# rgb_corin.net
KiCad netlist of a schematic drawn in Altium Designer
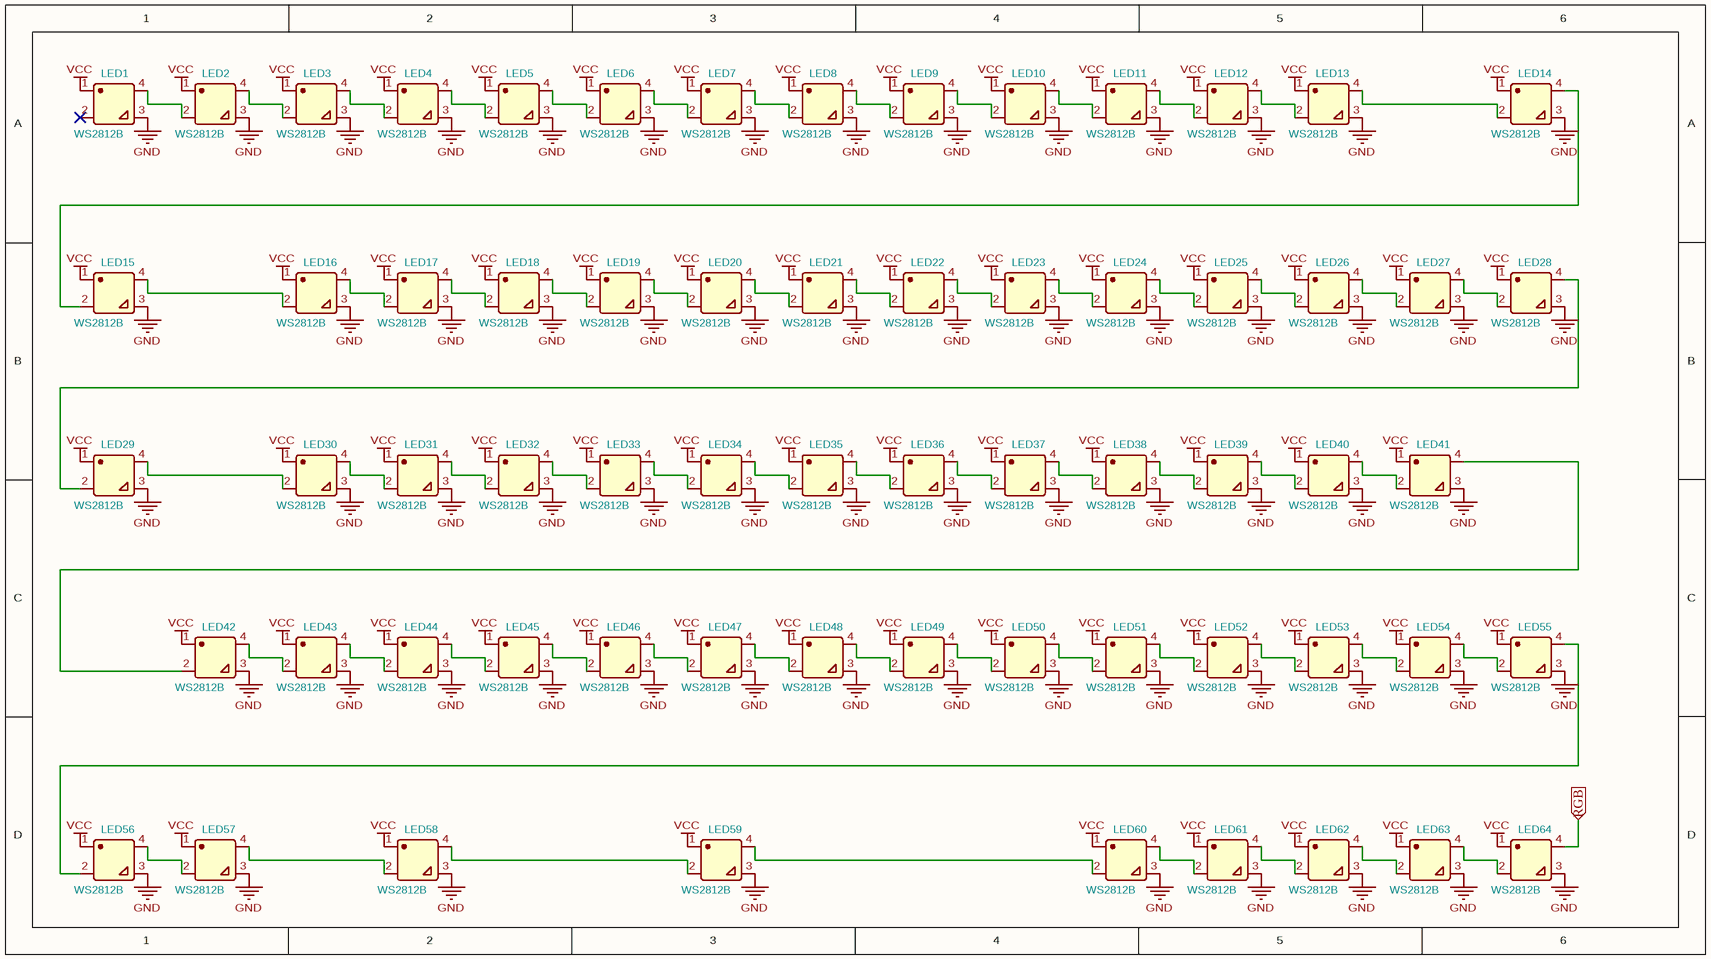
[diagram p0: rgb_corin.schdoc]

(export (version "E")
  (design (tool "Eeschema 10.0.6"))
  (components
    (comp (ref "LED1")
      (value "WS2812B")
      (fields (field (name "CONTRIBUTOR") "Longnald"))
      (libsource (lib "altium-import") (part "root_0_WS2812B_"))
    )
    (comp (ref "LED2")
      (value "WS2812B")
      (fields (field (name "CONTRIBUTOR") "Longnald"))
      (libsource (lib "altium-import") (part "root_0_WS2812B_"))
    )
    (comp (ref "LED3")
      (value "WS2812B")
      (fields (field (name "CONTRIBUTOR") "Longnald"))
      (libsource (lib "altium-import") (part "root_0_WS2812B_"))
    )
    (comp (ref "LED4")
      (value "WS2812B")
      (fields (field (name "CONTRIBUTOR") "Longnald"))
      (libsource (lib "altium-import") (part "root_0_WS2812B_"))
    )
    (comp (ref "LED5")
      (value "WS2812B")
      (fields (field (name "CONTRIBUTOR") "Longnald"))
      (libsource (lib "altium-import") (part "root_0_WS2812B_"))
    )
    (comp (ref "LED6")
      (value "WS2812B")
      (fields (field (name "CONTRIBUTOR") "Longnald"))
      (libsource (lib "altium-import") (part "root_0_WS2812B_"))
    )
    (comp (ref "LED7")
      (value "WS2812B")
      (fields (field (name "CONTRIBUTOR") "Longnald"))
      (libsource (lib "altium-import") (part "root_0_WS2812B_"))
    )
    (comp (ref "LED8")
      (value "WS2812B")
      (fields (field (name "CONTRIBUTOR") "Longnald"))
      (libsource (lib "altium-import") (part "root_0_WS2812B_"))
    )
    (comp (ref "LED9")
      (value "WS2812B")
      (fields (field (name "CONTRIBUTOR") "Longnald"))
      (libsource (lib "altium-import") (part "root_0_WS2812B_"))
    )
    (comp (ref "LED10")
      (value "WS2812B")
      (fields (field (name "CONTRIBUTOR") "Longnald"))
      (libsource (lib "altium-import") (part "root_0_WS2812B_"))
    )
    (comp (ref "LED11")
      (value "WS2812B")
      (fields (field (name "CONTRIBUTOR") "Longnald"))
      (libsource (lib "altium-import") (part "root_0_WS2812B_"))
    )
    (comp (ref "LED12")
      (value "WS2812B")
      (fields (field (name "CONTRIBUTOR") "Longnald"))
      (libsource (lib "altium-import") (part "root_0_WS2812B_"))
    )
    (comp (ref "LED13")
      (value "WS2812B")
      (fields (field (name "CONTRIBUTOR") "Longnald"))
      (libsource (lib "altium-import") (part "root_0_WS2812B_"))
    )
    (comp (ref "LED14")
      (value "WS2812B")
      (fields (field (name "CONTRIBUTOR") "Longnald"))
      (libsource (lib "altium-import") (part "root_0_WS2812B_"))
    )
    (comp (ref "LED15")
      (value "WS2812B")
      (fields (field (name "CONTRIBUTOR") "Longnald"))
      (libsource (lib "altium-import") (part "root_0_WS2812B_"))
    )
    (comp (ref "LED16")
      (value "WS2812B")
      (fields (field (name "CONTRIBUTOR") "Longnald"))
      (libsource (lib "altium-import") (part "root_0_WS2812B_"))
    )
    (comp (ref "LED17")
      (value "WS2812B")
      (fields (field (name "CONTRIBUTOR") "Longnald"))
      (libsource (lib "altium-import") (part "root_0_WS2812B_"))
    )
    (comp (ref "LED18")
      (value "WS2812B")
      (fields (field (name "CONTRIBUTOR") "Longnald"))
      (libsource (lib "altium-import") (part "root_0_WS2812B_"))
    )
    (comp (ref "LED19")
      (value "WS2812B")
      (fields (field (name "CONTRIBUTOR") "Longnald"))
      (libsource (lib "altium-import") (part "root_0_WS2812B_"))
    )
    (comp (ref "LED20")
      (value "WS2812B")
      (fields (field (name "CONTRIBUTOR") "Longnald"))
      (libsource (lib "altium-import") (part "root_0_WS2812B_"))
    )
    (comp (ref "LED21")
      (value "WS2812B")
      (fields (field (name "CONTRIBUTOR") "Longnald"))
      (libsource (lib "altium-import") (part "root_0_WS2812B_"))
    )
    (comp (ref "LED22")
      (value "WS2812B")
      (fields (field (name "CONTRIBUTOR") "Longnald"))
      (libsource (lib "altium-import") (part "root_0_WS2812B_"))
    )
    (comp (ref "LED23")
      (value "WS2812B")
      (fields (field (name "CONTRIBUTOR") "Longnald"))
      (libsource (lib "altium-import") (part "root_0_WS2812B_"))
    )
    (comp (ref "LED24")
      (value "WS2812B")
      (fields (field (name "CONTRIBUTOR") "Longnald"))
      (libsource (lib "altium-import") (part "root_0_WS2812B_"))
    )
    (comp (ref "LED25")
      (value "WS2812B")
      (fields (field (name "CONTRIBUTOR") "Longnald"))
      (libsource (lib "altium-import") (part "root_0_WS2812B_"))
    )
    (comp (ref "LED26")
      (value "WS2812B")
      (fields (field (name "CONTRIBUTOR") "Longnald"))
      (libsource (lib "altium-import") (part "root_0_WS2812B_"))
    )
    (comp (ref "LED27")
      (value "WS2812B")
      (fields (field (name "CONTRIBUTOR") "Longnald"))
      (libsource (lib "altium-import") (part "root_0_WS2812B_"))
    )
    (comp (ref "LED28")
      (value "WS2812B")
      (fields (field (name "CONTRIBUTOR") "Longnald"))
      (libsource (lib "altium-import") (part "root_0_WS2812B_"))
    )
    (comp (ref "LED29")
      (value "WS2812B")
      (fields (field (name "CONTRIBUTOR") "Longnald"))
      (libsource (lib "altium-import") (part "root_0_WS2812B_"))
    )
    (comp (ref "LED30")
      (value "WS2812B")
      (fields (field (name "CONTRIBUTOR") "Longnald"))
      (libsource (lib "altium-import") (part "root_0_WS2812B_"))
    )
    (comp (ref "LED31")
      (value "WS2812B")
      (fields (field (name "CONTRIBUTOR") "Longnald"))
      (libsource (lib "altium-import") (part "root_0_WS2812B_"))
    )
    (comp (ref "LED32")
      (value "WS2812B")
      (fields (field (name "CONTRIBUTOR") "Longnald"))
      (libsource (lib "altium-import") (part "root_0_WS2812B_"))
    )
    (comp (ref "LED33")
      (value "WS2812B")
      (fields (field (name "CONTRIBUTOR") "Longnald"))
      (libsource (lib "altium-import") (part "root_0_WS2812B_"))
    )
    (comp (ref "LED34")
      (value "WS2812B")
      (fields (field (name "CONTRIBUTOR") "Longnald"))
      (libsource (lib "altium-import") (part "root_0_WS2812B_"))
    )
    (comp (ref "LED35")
      (value "WS2812B")
      (fields (field (name "CONTRIBUTOR") "Longnald"))
      (libsource (lib "altium-import") (part "root_0_WS2812B_"))
    )
    (comp (ref "LED36")
      (value "WS2812B")
      (fields (field (name "CONTRIBUTOR") "Longnald"))
      (libsource (lib "altium-import") (part "root_0_WS2812B_"))
    )
    (comp (ref "LED37")
      (value "WS2812B")
      (fields (field (name "CONTRIBUTOR") "Longnald"))
      (libsource (lib "altium-import") (part "root_0_WS2812B_"))
    )
    (comp (ref "LED38")
      (value "WS2812B")
      (fields (field (name "CONTRIBUTOR") "Longnald"))
      (libsource (lib "altium-import") (part "root_0_WS2812B_"))
    )
    (comp (ref "LED39")
      (value "WS2812B")
      (fields (field (name "CONTRIBUTOR") "Longnald"))
      (libsource (lib "altium-import") (part "root_0_WS2812B_"))
    )
    (comp (ref "LED40")
      (value "WS2812B")
      (fields (field (name "CONTRIBUTOR") "Longnald"))
      (libsource (lib "altium-import") (part "root_0_WS2812B_"))
    )
    (comp (ref "LED41")
      (value "WS2812B")
      (fields (field (name "CONTRIBUTOR") "Longnald"))
      (libsource (lib "altium-import") (part "root_0_WS2812B_"))
    )
    (comp (ref "LED42")
      (value "WS2812B")
      (fields (field (name "CONTRIBUTOR") "Longnald"))
      (libsource (lib "altium-import") (part "root_0_WS2812B_"))
    )
    (comp (ref "LED43")
      (value "WS2812B")
      (fields (field (name "CONTRIBUTOR") "Longnald"))
      (libsource (lib "altium-import") (part "root_0_WS2812B_"))
    )
    (comp (ref "LED44")
      (value "WS2812B")
      (fields (field (name "CONTRIBUTOR") "Longnald"))
      (libsource (lib "altium-import") (part "root_0_WS2812B_"))
    )
    (comp (ref "LED45")
      (value "WS2812B")
      (fields (field (name "CONTRIBUTOR") "Longnald"))
      (libsource (lib "altium-import") (part "root_0_WS2812B_"))
    )
    (comp (ref "LED46")
      (value "WS2812B")
      (fields (field (name "CONTRIBUTOR") "Longnald"))
      (libsource (lib "altium-import") (part "root_0_WS2812B_"))
    )
    (comp (ref "LED47")
      (value "WS2812B")
      (fields (field (name "CONTRIBUTOR") "Longnald"))
      (libsource (lib "altium-import") (part "root_0_WS2812B_"))
    )
    (comp (ref "LED48")
      (value "WS2812B")
      (fields (field (name "CONTRIBUTOR") "Longnald"))
      (libsource (lib "altium-import") (part "root_0_WS2812B_"))
    )
    (comp (ref "LED49")
      (value "WS2812B")
      (fields (field (name "CONTRIBUTOR") "Longnald"))
      (libsource (lib "altium-import") (part "root_0_WS2812B_"))
    )
    (comp (ref "LED50")
      (value "WS2812B")
      (fields (field (name "CONTRIBUTOR") "Longnald"))
      (libsource (lib "altium-import") (part "root_0_WS2812B_"))
    )
    (comp (ref "LED51")
      (value "WS2812B")
      (fields (field (name "CONTRIBUTOR") "Longnald"))
      (libsource (lib "altium-import") (part "root_0_WS2812B_"))
    )
    (comp (ref "LED52")
      (value "WS2812B")
      (fields (field (name "CONTRIBUTOR") "Longnald"))
      (libsource (lib "altium-import") (part "root_0_WS2812B_"))
    )
    (comp (ref "LED53")
      (value "WS2812B")
      (fields (field (name "CONTRIBUTOR") "Longnald"))
      (libsource (lib "altium-import") (part "root_0_WS2812B_"))
    )
    (comp (ref "LED54")
      (value "WS2812B")
      (fields (field (name "CONTRIBUTOR") "Longnald"))
      (libsource (lib "altium-import") (part "root_0_WS2812B_"))
    )
    (comp (ref "LED55")
      (value "WS2812B")
      (fields (field (name "CONTRIBUTOR") "Longnald"))
      (libsource (lib "altium-import") (part "root_0_WS2812B_"))
    )
    (comp (ref "LED56")
      (value "WS2812B")
      (fields (field (name "CONTRIBUTOR") "Longnald"))
      (libsource (lib "altium-import") (part "root_0_WS2812B_"))
    )
    (comp (ref "LED57")
      (value "WS2812B")
      (fields (field (name "CONTRIBUTOR") "Longnald"))
      (libsource (lib "altium-import") (part "root_0_WS2812B_"))
    )
    (comp (ref "LED58")
      (value "WS2812B")
      (fields (field (name "CONTRIBUTOR") "Longnald"))
      (libsource (lib "altium-import") (part "root_0_WS2812B_"))
    )
    (comp (ref "LED59")
      (value "WS2812B")
      (fields (field (name "CONTRIBUTOR") "Longnald"))
      (libsource (lib "altium-import") (part "root_0_WS2812B_"))
    )
    (comp (ref "LED60")
      (value "WS2812B")
      (fields (field (name "CONTRIBUTOR") "Longnald"))
      (libsource (lib "altium-import") (part "root_0_WS2812B_"))
    )
    (comp (ref "LED61")
      (value "WS2812B")
      (fields (field (name "CONTRIBUTOR") "Longnald"))
      (libsource (lib "altium-import") (part "root_0_WS2812B_"))
    )
    (comp (ref "LED62")
      (value "WS2812B")
      (fields (field (name "CONTRIBUTOR") "Longnald"))
      (libsource (lib "altium-import") (part "root_0_WS2812B_"))
    )
    (comp (ref "LED63")
      (value "WS2812B")
      (fields (field (name "CONTRIBUTOR") "Longnald"))
      (libsource (lib "altium-import") (part "root_0_WS2812B_"))
    )
    (comp (ref "LED64")
      (value "WS2812B")
      (fields (field (name "CONTRIBUTOR") "Longnald"))
      (libsource (lib "altium-import") (part "root_0_WS2812B_"))
    )
  )
  (nets
    (net (code "1") (name "/RGB") (class "Default")
      (node (ref "LED64") (pin "4") (pinfunction "DIN_4") (pintype "passive"))
    )
    (net (code "2") (name "GND") (class "Default")
      (node (ref "LED1") (pin "3") (pinfunction "VSS_3") (pintype "passive"))
      (node (ref "LED10") (pin "3") (pinfunction "VSS_3") (pintype "passive"))
      (node (ref "LED11") (pin "3") (pinfunction "VSS_3") (pintype "passive"))
      (node (ref "LED12") (pin "3") (pinfunction "VSS_3") (pintype "passive"))
      (node (ref "LED13") (pin "3") (pinfunction "VSS_3") (pintype "passive"))
      (node (ref "LED14") (pin "3") (pinfunction "VSS_3") (pintype "passive"))
      (node (ref "LED15") (pin "3") (pinfunction "VSS_3") (pintype "passive"))
      (node (ref "LED16") (pin "3") (pinfunction "VSS_3") (pintype "passive"))
      (node (ref "LED17") (pin "3") (pinfunction "VSS_3") (pintype "passive"))
      (node (ref "LED18") (pin "3") (pinfunction "VSS_3") (pintype "passive"))
      (node (ref "LED19") (pin "3") (pinfunction "VSS_3") (pintype "passive"))
      (node (ref "LED2") (pin "3") (pinfunction "VSS_3") (pintype "passive"))
      (node (ref "LED20") (pin "3") (pinfunction "VSS_3") (pintype "passive"))
      (node (ref "LED21") (pin "3") (pinfunction "VSS_3") (pintype "passive"))
      (node (ref "LED22") (pin "3") (pinfunction "VSS_3") (pintype "passive"))
      (node (ref "LED23") (pin "3") (pinfunction "VSS_3") (pintype "passive"))
      (node (ref "LED24") (pin "3") (pinfunction "VSS_3") (pintype "passive"))
      (node (ref "LED25") (pin "3") (pinfunction "VSS_3") (pintype "passive"))
      (node (ref "LED26") (pin "3") (pinfunction "VSS_3") (pintype "passive"))
      (node (ref "LED27") (pin "3") (pinfunction "VSS_3") (pintype "passive"))
      (node (ref "LED28") (pin "3") (pinfunction "VSS_3") (pintype "passive"))
      (node (ref "LED29") (pin "3") (pinfunction "VSS_3") (pintype "passive"))
      (node (ref "LED3") (pin "3") (pinfunction "VSS_3") (pintype "passive"))
      (node (ref "LED30") (pin "3") (pinfunction "VSS_3") (pintype "passive"))
      (node (ref "LED31") (pin "3") (pinfunction "VSS_3") (pintype "passive"))
      (node (ref "LED32") (pin "3") (pinfunction "VSS_3") (pintype "passive"))
      (node (ref "LED33") (pin "3") (pinfunction "VSS_3") (pintype "passive"))
      (node (ref "LED34") (pin "3") (pinfunction "VSS_3") (pintype "passive"))
      (node (ref "LED35") (pin "3") (pinfunction "VSS_3") (pintype "passive"))
      (node (ref "LED36") (pin "3") (pinfunction "VSS_3") (pintype "passive"))
      (node (ref "LED37") (pin "3") (pinfunction "VSS_3") (pintype "passive"))
      (node (ref "LED38") (pin "3") (pinfunction "VSS_3") (pintype "passive"))
      (node (ref "LED39") (pin "3") (pinfunction "VSS_3") (pintype "passive"))
      (node (ref "LED4") (pin "3") (pinfunction "VSS_3") (pintype "passive"))
      (node (ref "LED40") (pin "3") (pinfunction "VSS_3") (pintype "passive"))
      (node (ref "LED41") (pin "3") (pinfunction "VSS_3") (pintype "passive"))
      (node (ref "LED42") (pin "3") (pinfunction "VSS_3") (pintype "passive"))
      (node (ref "LED43") (pin "3") (pinfunction "VSS_3") (pintype "passive"))
      (node (ref "LED44") (pin "3") (pinfunction "VSS_3") (pintype "passive"))
      (node (ref "LED45") (pin "3") (pinfunction "VSS_3") (pintype "passive"))
      (node (ref "LED46") (pin "3") (pinfunction "VSS_3") (pintype "passive"))
      (node (ref "LED47") (pin "3") (pinfunction "VSS_3") (pintype "passive"))
      (node (ref "LED48") (pin "3") (pinfunction "VSS_3") (pintype "passive"))
      (node (ref "LED49") (pin "3") (pinfunction "VSS_3") (pintype "passive"))
      (node (ref "LED5") (pin "3") (pinfunction "VSS_3") (pintype "passive"))
      (node (ref "LED50") (pin "3") (pinfunction "VSS_3") (pintype "passive"))
      (node (ref "LED51") (pin "3") (pinfunction "VSS_3") (pintype "passive"))
      (node (ref "LED52") (pin "3") (pinfunction "VSS_3") (pintype "passive"))
      (node (ref "LED53") (pin "3") (pinfunction "VSS_3") (pintype "passive"))
      (node (ref "LED54") (pin "3") (pinfunction "VSS_3") (pintype "passive"))
      (node (ref "LED55") (pin "3") (pinfunction "VSS_3") (pintype "passive"))
      (node (ref "LED56") (pin "3") (pinfunction "VSS_3") (pintype "passive"))
      (node (ref "LED57") (pin "3") (pinfunction "VSS_3") (pintype "passive"))
      (node (ref "LED58") (pin "3") (pinfunction "VSS_3") (pintype "passive"))
      (node (ref "LED59") (pin "3") (pinfunction "VSS_3") (pintype "passive"))
      (node (ref "LED6") (pin "3") (pinfunction "VSS_3") (pintype "passive"))
      (node (ref "LED60") (pin "3") (pinfunction "VSS_3") (pintype "passive"))
      (node (ref "LED61") (pin "3") (pinfunction "VSS_3") (pintype "passive"))
      (node (ref "LED62") (pin "3") (pinfunction "VSS_3") (pintype "passive"))
      (node (ref "LED63") (pin "3") (pinfunction "VSS_3") (pintype "passive"))
      (node (ref "LED64") (pin "3") (pinfunction "VSS_3") (pintype "passive"))
      (node (ref "LED7") (pin "3") (pinfunction "VSS_3") (pintype "passive"))
      (node (ref "LED8") (pin "3") (pinfunction "VSS_3") (pintype "passive"))
      (node (ref "LED9") (pin "3") (pinfunction "VSS_3") (pintype "passive"))
    )
    (net (code "3") (name "Net-(LED1-DIN)") (class "Default")
      (node (ref "LED1") (pin "4") (pinfunction "DIN_4") (pintype "passive"))
      (node (ref "LED2") (pin "2") (pinfunction "DOUT_2") (pintype "passive"))
    )
    (net (code "4") (name "Net-(LED2-DIN)") (class "Default")
      (node (ref "LED2") (pin "4") (pinfunction "DIN_4") (pintype "passive"))
      (node (ref "LED3") (pin "2") (pinfunction "DOUT_2") (pintype "passive"))
    )
    (net (code "5") (name "Net-(LED3-DIN)") (class "Default")
      (node (ref "LED3") (pin "4") (pinfunction "DIN_4") (pintype "passive"))
      (node (ref "LED4") (pin "2") (pinfunction "DOUT_2") (pintype "passive"))
    )
    (net (code "6") (name "Net-(LED4-DIN)") (class "Default")
      (node (ref "LED4") (pin "4") (pinfunction "DIN_4") (pintype "passive"))
      (node (ref "LED5") (pin "2") (pinfunction "DOUT_2") (pintype "passive"))
    )
    (net (code "7") (name "Net-(LED5-DIN)") (class "Default")
      (node (ref "LED5") (pin "4") (pinfunction "DIN_4") (pintype "passive"))
      (node (ref "LED6") (pin "2") (pinfunction "DOUT_2") (pintype "passive"))
    )
    (net (code "8") (name "Net-(LED6-DIN)") (class "Default")
      (node (ref "LED6") (pin "4") (pinfunction "DIN_4") (pintype "passive"))
      (node (ref "LED7") (pin "2") (pinfunction "DOUT_2") (pintype "passive"))
    )
    (net (code "9") (name "Net-(LED7-DIN)") (class "Default")
      (node (ref "LED7") (pin "4") (pinfunction "DIN_4") (pintype "passive"))
      (node (ref "LED8") (pin "2") (pinfunction "DOUT_2") (pintype "passive"))
    )
    (net (code "10") (name "Net-(LED8-DIN)") (class "Default")
      (node (ref "LED8") (pin "4") (pinfunction "DIN_4") (pintype "passive"))
      (node (ref "LED9") (pin "2") (pinfunction "DOUT_2") (pintype "passive"))
    )
    (net (code "11") (name "Net-(LED10-DIN)") (class "Default")
      (node (ref "LED10") (pin "4") (pinfunction "DIN_4") (pintype "passive"))
      (node (ref "LED11") (pin "2") (pinfunction "DOUT_2") (pintype "passive"))
    )
    (net (code "12") (name "Net-(LED10-DOUT)") (class "Default")
      (node (ref "LED10") (pin "2") (pinfunction "DOUT_2") (pintype "passive"))
      (node (ref "LED9") (pin "4") (pinfunction "DIN_4") (pintype "passive"))
    )
    (net (code "13") (name "Net-(LED11-DIN)") (class "Default")
      (node (ref "LED11") (pin "4") (pinfunction "DIN_4") (pintype "passive"))
      (node (ref "LED12") (pin "2") (pinfunction "DOUT_2") (pintype "passive"))
    )
    (net (code "14") (name "Net-(LED12-DIN)") (class "Default")
      (node (ref "LED12") (pin "4") (pinfunction "DIN_4") (pintype "passive"))
      (node (ref "LED13") (pin "2") (pinfunction "DOUT_2") (pintype "passive"))
    )
    (net (code "15") (name "Net-(LED13-DIN)") (class "Default")
      (node (ref "LED13") (pin "4") (pinfunction "DIN_4") (pintype "passive"))
      (node (ref "LED14") (pin "2") (pinfunction "DOUT_2") (pintype "passive"))
    )
    (net (code "16") (name "Net-(LED14-DIN)") (class "Default")
      (node (ref "LED14") (pin "4") (pinfunction "DIN_4") (pintype "passive"))
      (node (ref "LED15") (pin "2") (pinfunction "DOUT_2") (pintype "passive"))
    )
    (net (code "17") (name "Net-(LED15-DIN)") (class "Default")
      (node (ref "LED15") (pin "4") (pinfunction "DIN_4") (pintype "passive"))
      (node (ref "LED16") (pin "2") (pinfunction "DOUT_2") (pintype "passive"))
    )
    (net (code "18") (name "Net-(LED16-DIN)") (class "Default")
      (node (ref "LED16") (pin "4") (pinfunction "DIN_4") (pintype "passive"))
      (node (ref "LED17") (pin "2") (pinfunction "DOUT_2") (pintype "passive"))
    )
    (net (code "19") (name "Net-(LED17-DIN)") (class "Default")
      (node (ref "LED17") (pin "4") (pinfunction "DIN_4") (pintype "passive"))
      (node (ref "LED18") (pin "2") (pinfunction "DOUT_2") (pintype "passive"))
    )
    (net (code "20") (name "Net-(LED18-DIN)") (class "Default")
      (node (ref "LED18") (pin "4") (pinfunction "DIN_4") (pintype "passive"))
      (node (ref "LED19") (pin "2") (pinfunction "DOUT_2") (pintype "passive"))
    )
    (net (code "21") (name "Net-(LED19-DIN)") (class "Default")
      (node (ref "LED19") (pin "4") (pinfunction "DIN_4") (pintype "passive"))
      (node (ref "LED20") (pin "2") (pinfunction "DOUT_2") (pintype "passive"))
    )
    (net (code "22") (name "Net-(LED20-DIN)") (class "Default")
      (node (ref "LED20") (pin "4") (pinfunction "DIN_4") (pintype "passive"))
      (node (ref "LED21") (pin "2") (pinfunction "DOUT_2") (pintype "passive"))
    )
    (net (code "23") (name "Net-(LED21-DIN)") (class "Default")
      (node (ref "LED21") (pin "4") (pinfunction "DIN_4") (pintype "passive"))
      (node (ref "LED22") (pin "2") (pinfunction "DOUT_2") (pintype "passive"))
    )
    (net (code "24") (name "Net-(LED22-DIN)") (class "Default")
      (node (ref "LED22") (pin "4") (pinfunction "DIN_4") (pintype "passive"))
      (node (ref "LED23") (pin "2") (pinfunction "DOUT_2") (pintype "passive"))
    )
    (net (code "25") (name "Net-(LED23-DIN)") (class "Default")
      (node (ref "LED23") (pin "4") (pinfunction "DIN_4") (pintype "passive"))
      (node (ref "LED24") (pin "2") (pinfunction "DOUT_2") (pintype "passive"))
    )
    (net (code "26") (name "Net-(LED24-DIN)") (class "Default")
      (node (ref "LED24") (pin "4") (pinfunction "DIN_4") (pintype "passive"))
      (node (ref "LED25") (pin "2") (pinfunction "DOUT_2") (pintype "passive"))
    )
    (net (code "27") (name "Net-(LED25-DIN)") (class "Default")
      (node (ref "LED25") (pin "4") (pinfunction "DIN_4") (pintype "passive"))
      (node (ref "LED26") (pin "2") (pinfunction "DOUT_2") (pintype "passive"))
    )
    (net (code "28") (name "Net-(LED26-DIN)") (class "Default")
      (node (ref "LED26") (pin "4") (pinfunction "DIN_4") (pintype "passive"))
      (node (ref "LED27") (pin "2") (pinfunction "DOUT_2") (pintype "passive"))
    )
    (net (code "29") (name "Net-(LED27-DIN)") (class "Default")
      (node (ref "LED27") (pin "4") (pinfunction "DIN_4") (pintype "passive"))
      (node (ref "LED28") (pin "2") (pinfunction "DOUT_2") (pintype "passive"))
    )
    (net (code "30") (name "Net-(LED28-DIN)") (class "Default")
      (node (ref "LED28") (pin "4") (pinfunction "DIN_4") (pintype "passive"))
      (node (ref "LED29") (pin "2") (pinfunction "DOUT_2") (pintype "passive"))
    )
    (net (code "31") (name "Net-(LED29-DIN)") (class "Default")
      (node (ref "LED29") (pin "4") (pinfunction "DIN_4") (pintype "passive"))
      (node (ref "LED30") (pin "2") (pinfunction "DOUT_2") (pintype "passive"))
    )
    (net (code "32") (name "Net-(LED30-DIN)") (class "Default")
      (node (ref "LED30") (pin "4") (pinfunction "DIN_4") (pintype "passive"))
      (node (ref "LED31") (pin "2") (pinfunction "DOUT_2") (pintype "passive"))
    )
    (net (code "33") (name "Net-(LED31-DIN)") (class "Default")
      (node (ref "LED31") (pin "4") (pinfunction "DIN_4") (pintype "passive"))
      (node (ref "LED32") (pin "2") (pinfunction "DOUT_2") (pintype "passive"))
    )
    (net (code "34") (name "Net-(LED32-DIN)") (class "Default")
      (node (ref "LED32") (pin "4") (pinfunction "DIN_4") (pintype "passive"))
      (node (ref "LED33") (pin "2") (pinfunction "DOUT_2") (pintype "passive"))
    )
    (net (code "35") (name "Net-(LED33-DIN)") (class "Default")
      (node (ref "LED33") (pin "4") (pinfunction "DIN_4") (pintype "passive"))
      (node (ref "LED34") (pin "2") (pinfunction "DOUT_2") (pintype "passive"))
    )
    (net (code "36") (name "Net-(LED34-DIN)") (class "Default")
      (node (ref "LED34") (pin "4") (pinfunction "DIN_4") (pintype "passive"))
      (node (ref "LED35") (pin "2") (pinfunction "DOUT_2") (pintype "passive"))
    )
    (net (code "37") (name "Net-(LED35-DIN)") (class "Default")
      (node (ref "LED35") (pin "4") (pinfunction "DIN_4") (pintype "passive"))
      (node (ref "LED36") (pin "2") (pinfunction "DOUT_2") (pintype "passive"))
    )
    (net (code "38") (name "Net-(LED36-DIN)") (class "Default")
      (node (ref "LED36") (pin "4") (pinfunction "DIN_4") (pintype "passive"))
      (node (ref "LED37") (pin "2") (pinfunction "DOUT_2") (pintype "passive"))
    )
    (net (code "39") (name "Net-(LED37-DIN)") (class "Default")
      (node (ref "LED37") (pin "4") (pinfunction "DIN_4") (pintype "passive"))
      (node (ref "LED38") (pin "2") (pinfunction "DOUT_2") (pintype "passive"))
    )
    (net (code "40") (name "Net-(LED38-DIN)") (class "Default")
      (node (ref "LED38") (pin "4") (pinfunction "DIN_4") (pintype "passive"))
      (node (ref "LED39") (pin "2") (pinfunction "DOUT_2") (pintype "passive"))
    )
    (net (code "41") (name "Net-(LED39-DIN)") (class "Default")
      (node (ref "LED39") (pin "4") (pinfunction "DIN_4") (pintype "passive"))
      (node (ref "LED40") (pin "2") (pinfunction "DOUT_2") (pintype "passive"))
    )
    (net (code "42") (name "Net-(LED40-DIN)") (class "Default")
      (node (ref "LED40") (pin "4") (pinfunction "DIN_4") (pintype "passive"))
      (node (ref "LED41") (pin "2") (pinfunction "DOUT_2") (pintype "passive"))
    )
    (net (code "43") (name "Net-(LED41-DIN)") (class "Default")
      (node (ref "LED41") (pin "4") (pinfunction "DIN_4") (pintype "passive"))
      (node (ref "LED42") (pin "2") (pinfunction "DOUT_2") (pintype "passive"))
    )
    (net (code "44") (name "Net-(LED42-DIN)") (class "Default")
      (node (ref "LED42") (pin "4") (pinfunction "DIN_4") (pintype "passive"))
      (node (ref "LED43") (pin "2") (pinfunction "DOUT_2") (pintype "passive"))
    )
    (net (code "45") (name "Net-(LED43-DIN)") (class "Default")
      (node (ref "LED43") (pin "4") (pinfunction "DIN_4") (pintype "passive"))
      (node (ref "LED44") (pin "2") (pinfunction "DOUT_2") (pintype "passive"))
    )
    (net (code "46") (name "Net-(LED44-DIN)") (class "Default")
      (node (ref "LED44") (pin "4") (pinfunction "DIN_4") (pintype "passive"))
      (node (ref "LED45") (pin "2") (pinfunction "DOUT_2") (pintype "passive"))
    )
    (net (code "47") (name "Net-(LED45-DIN)") (class "Default")
      (node (ref "LED45") (pin "4") (pinfunction "DIN_4") (pintype "passive"))
      (node (ref "LED46") (pin "2") (pinfunction "DOUT_2") (pintype "passive"))
    )
    (net (code "48") (name "Net-(LED46-DIN)") (class "Default")
      (node (ref "LED46") (pin "4") (pinfunction "DIN_4") (pintype "passive"))
      (node (ref "LED47") (pin "2") (pinfunction "DOUT_2") (pintype "passive"))
    )
    (net (code "49") (name "Net-(LED47-DIN)") (class "Default")
      (node (ref "LED47") (pin "4") (pinfunction "DIN_4") (pintype "passive"))
      (node (ref "LED48") (pin "2") (pinfunction "DOUT_2") (pintype "passive"))
    )
    (net (code "50") (name "Net-(LED48-DIN)") (class "Default")
      (node (ref "LED48") (pin "4") (pinfunction "DIN_4") (pintype "passive"))
      (node (ref "LED49") (pin "2") (pinfunction "DOUT_2") (pintype "passive"))
    )
    (net (code "51") (name "Net-(LED49-DIN)") (class "Default")
      (node (ref "LED49") (pin "4") (pinfunction "DIN_4") (pintype "passive"))
      (node (ref "LED50") (pin "2") (pinfunction "DOUT_2") (pintype "passive"))
    )
    (net (code "52") (name "Net-(LED50-DIN)") (class "Default")
      (node (ref "LED50") (pin "4") (pinfunction "DIN_4") (pintype "passive"))
      (node (ref "LED51") (pin "2") (pinfunction "DOUT_2") (pintype "passive"))
    )
    (net (code "53") (name "Net-(LED51-DIN)") (class "Default")
      (node (ref "LED51") (pin "4") (pinfunction "DIN_4") (pintype "passive"))
      (node (ref "LED52") (pin "2") (pinfunction "DOUT_2") (pintype "passive"))
    )
    (net (code "54") (name "Net-(LED52-DIN)") (class "Default")
      (node (ref "LED52") (pin "4") (pinfunction "DIN_4") (pintype "passive"))
      (node (ref "LED53") (pin "2") (pinfunction "DOUT_2") (pintype "passive"))
    )
    (net (code "55") (name "Net-(LED53-DIN)") (class "Default")
      (node (ref "LED53") (pin "4") (pinfunction "DIN_4") (pintype "passive"))
      (node (ref "LED54") (pin "2") (pinfunction "DOUT_2") (pintype "passive"))
    )
    (net (code "56") (name "Net-(LED54-DIN)") (class "Default")
      (node (ref "LED54") (pin "4") (pinfunction "DIN_4") (pintype "passive"))
      (node (ref "LED55") (pin "2") (pinfunction "DOUT_2") (pintype "passive"))
    )
    (net (code "57") (name "Net-(LED55-DIN)") (class "Default")
      (node (ref "LED55") (pin "4") (pinfunction "DIN_4") (pintype "passive"))
      (node (ref "LED56") (pin "2") (pinfunction "DOUT_2") (pintype "passive"))
    )
    (net (code "58") (name "Net-(LED56-DIN)") (class "Default")
      (node (ref "LED56") (pin "4") (pinfunction "DIN_4") (pintype "passive"))
      (node (ref "LED57") (pin "2") (pinfunction "DOUT_2") (pintype "passive"))
    )
    (net (code "59") (name "Net-(LED57-DIN)") (class "Default")
      (node (ref "LED57") (pin "4") (pinfunction "DIN_4") (pintype "passive"))
      (node (ref "LED58") (pin "2") (pinfunction "DOUT_2") (pintype "passive"))
    )
    (net (code "60") (name "Net-(LED58-DIN)") (class "Default")
      (node (ref "LED58") (pin "4") (pinfunction "DIN_4") (pintype "passive"))
      (node (ref "LED59") (pin "2") (pinfunction "DOUT_2") (pintype "passive"))
    )
    (net (code "61") (name "Net-(LED59-DIN)") (class "Default")
      (node (ref "LED59") (pin "4") (pinfunction "DIN_4") (pintype "passive"))
      (node (ref "LED60") (pin "2") (pinfunction "DOUT_2") (pintype "passive"))
    )
    (net (code "62") (name "Net-(LED60-DIN)") (class "Default")
      (node (ref "LED60") (pin "4") (pinfunction "DIN_4") (pintype "passive"))
      (node (ref "LED61") (pin "2") (pinfunction "DOUT_2") (pintype "passive"))
    )
    (net (code "63") (name "Net-(LED61-DIN)") (class "Default")
      (node (ref "LED61") (pin "4") (pinfunction "DIN_4") (pintype "passive"))
      (node (ref "LED62") (pin "2") (pinfunction "DOUT_2") (pintype "passive"))
    )
    (net (code "64") (name "Net-(LED62-DIN)") (class "Default")
      (node (ref "LED62") (pin "4") (pinfunction "DIN_4") (pintype "passive"))
      (node (ref "LED63") (pin "2") (pinfunction "DOUT_2") (pintype "passive"))
    )
    (net (code "65") (name "Net-(LED63-DIN)") (class "Default")
      (node (ref "LED63") (pin "4") (pinfunction "DIN_4") (pintype "passive"))
      (node (ref "LED64") (pin "2") (pinfunction "DOUT_2") (pintype "passive"))
    )
    (net (code "66") (name "VCC") (class "Default")
      (node (ref "LED1") (pin "1") (pinfunction "VDD_1") (pintype "passive"))
      (node (ref "LED10") (pin "1") (pinfunction "VDD_1") (pintype "passive"))
      (node (ref "LED11") (pin "1") (pinfunction "VDD_1") (pintype "passive"))
      (node (ref "LED12") (pin "1") (pinfunction "VDD_1") (pintype "passive"))
      (node (ref "LED13") (pin "1") (pinfunction "VDD_1") (pintype "passive"))
      (node (ref "LED14") (pin "1") (pinfunction "VDD_1") (pintype "passive"))
      (node (ref "LED15") (pin "1") (pinfunction "VDD_1") (pintype "passive"))
      (node (ref "LED16") (pin "1") (pinfunction "VDD_1") (pintype "passive"))
      (node (ref "LED17") (pin "1") (pinfunction "VDD_1") (pintype "passive"))
      (node (ref "LED18") (pin "1") (pinfunction "VDD_1") (pintype "passive"))
      (node (ref "LED19") (pin "1") (pinfunction "VDD_1") (pintype "passive"))
      (node (ref "LED2") (pin "1") (pinfunction "VDD_1") (pintype "passive"))
      (node (ref "LED20") (pin "1") (pinfunction "VDD_1") (pintype "passive"))
      (node (ref "LED21") (pin "1") (pinfunction "VDD_1") (pintype "passive"))
      (node (ref "LED22") (pin "1") (pinfunction "VDD_1") (pintype "passive"))
      (node (ref "LED23") (pin "1") (pinfunction "VDD_1") (pintype "passive"))
      (node (ref "LED24") (pin "1") (pinfunction "VDD_1") (pintype "passive"))
      (node (ref "LED25") (pin "1") (pinfunction "VDD_1") (pintype "passive"))
      (node (ref "LED26") (pin "1") (pinfunction "VDD_1") (pintype "passive"))
      (node (ref "LED27") (pin "1") (pinfunction "VDD_1") (pintype "passive"))
      (node (ref "LED28") (pin "1") (pinfunction "VDD_1") (pintype "passive"))
      (node (ref "LED29") (pin "1") (pinfunction "VDD_1") (pintype "passive"))
      (node (ref "LED3") (pin "1") (pinfunction "VDD_1") (pintype "passive"))
      (node (ref "LED30") (pin "1") (pinfunction "VDD_1") (pintype "passive"))
      (node (ref "LED31") (pin "1") (pinfunction "VDD_1") (pintype "passive"))
      (node (ref "LED32") (pin "1") (pinfunction "VDD_1") (pintype "passive"))
      (node (ref "LED33") (pin "1") (pinfunction "VDD_1") (pintype "passive"))
      (node (ref "LED34") (pin "1") (pinfunction "VDD_1") (pintype "passive"))
      (node (ref "LED35") (pin "1") (pinfunction "VDD_1") (pintype "passive"))
      (node (ref "LED36") (pin "1") (pinfunction "VDD_1") (pintype "passive"))
      (node (ref "LED37") (pin "1") (pinfunction "VDD_1") (pintype "passive"))
      (node (ref "LED38") (pin "1") (pinfunction "VDD_1") (pintype "passive"))
      (node (ref "LED39") (pin "1") (pinfunction "VDD_1") (pintype "passive"))
      (node (ref "LED4") (pin "1") (pinfunction "VDD_1") (pintype "passive"))
      (node (ref "LED40") (pin "1") (pinfunction "VDD_1") (pintype "passive"))
      (node (ref "LED41") (pin "1") (pinfunction "VDD_1") (pintype "passive"))
      (node (ref "LED42") (pin "1") (pinfunction "VDD_1") (pintype "passive"))
      (node (ref "LED43") (pin "1") (pinfunction "VDD_1") (pintype "passive"))
      (node (ref "LED44") (pin "1") (pinfunction "VDD_1") (pintype "passive"))
      (node (ref "LED45") (pin "1") (pinfunction "VDD_1") (pintype "passive"))
      (node (ref "LED46") (pin "1") (pinfunction "VDD_1") (pintype "passive"))
      (node (ref "LED47") (pin "1") (pinfunction "VDD_1") (pintype "passive"))
      (node (ref "LED48") (pin "1") (pinfunction "VDD_1") (pintype "passive"))
      (node (ref "LED49") (pin "1") (pinfunction "VDD_1") (pintype "passive"))
      (node (ref "LED5") (pin "1") (pinfunction "VDD_1") (pintype "passive"))
      (node (ref "LED50") (pin "1") (pinfunction "VDD_1") (pintype "passive"))
      (node (ref "LED51") (pin "1") (pinfunction "VDD_1") (pintype "passive"))
      (node (ref "LED52") (pin "1") (pinfunction "VDD_1") (pintype "passive"))
      (node (ref "LED53") (pin "1") (pinfunction "VDD_1") (pintype "passive"))
      (node (ref "LED54") (pin "1") (pinfunction "VDD_1") (pintype "passive"))
      (node (ref "LED55") (pin "1") (pinfunction "VDD_1") (pintype "passive"))
      (node (ref "LED56") (pin "1") (pinfunction "VDD_1") (pintype "passive"))
      (node (ref "LED57") (pin "1") (pinfunction "VDD_1") (pintype "passive"))
      (node (ref "LED58") (pin "1") (pinfunction "VDD_1") (pintype "passive"))
      (node (ref "LED59") (pin "1") (pinfunction "VDD_1") (pintype "passive"))
      (node (ref "LED6") (pin "1") (pinfunction "VDD_1") (pintype "passive"))
      (node (ref "LED60") (pin "1") (pinfunction "VDD_1") (pintype "passive"))
      (node (ref "LED61") (pin "1") (pinfunction "VDD_1") (pintype "passive"))
      (node (ref "LED62") (pin "1") (pinfunction "VDD_1") (pintype "passive"))
      (node (ref "LED63") (pin "1") (pinfunction "VDD_1") (pintype "passive"))
      (node (ref "LED64") (pin "1") (pinfunction "VDD_1") (pintype "passive"))
      (node (ref "LED7") (pin "1") (pinfunction "VDD_1") (pintype "passive"))
      (node (ref "LED8") (pin "1") (pinfunction "VDD_1") (pintype "passive"))
      (node (ref "LED9") (pin "1") (pinfunction "VDD_1") (pintype "passive"))
    )
    (net (code "67") (name "unconnected-(LED1-DOUT-Pad2)") (class "Default")
      (node (ref "LED1") (pin "2") (pinfunction "DOUT_2") (pintype "passive+no_connect"))
    )
  )
)
